# lidar_made_by_apple.net
KiCad netlist of a schematic drawn in EAGLE
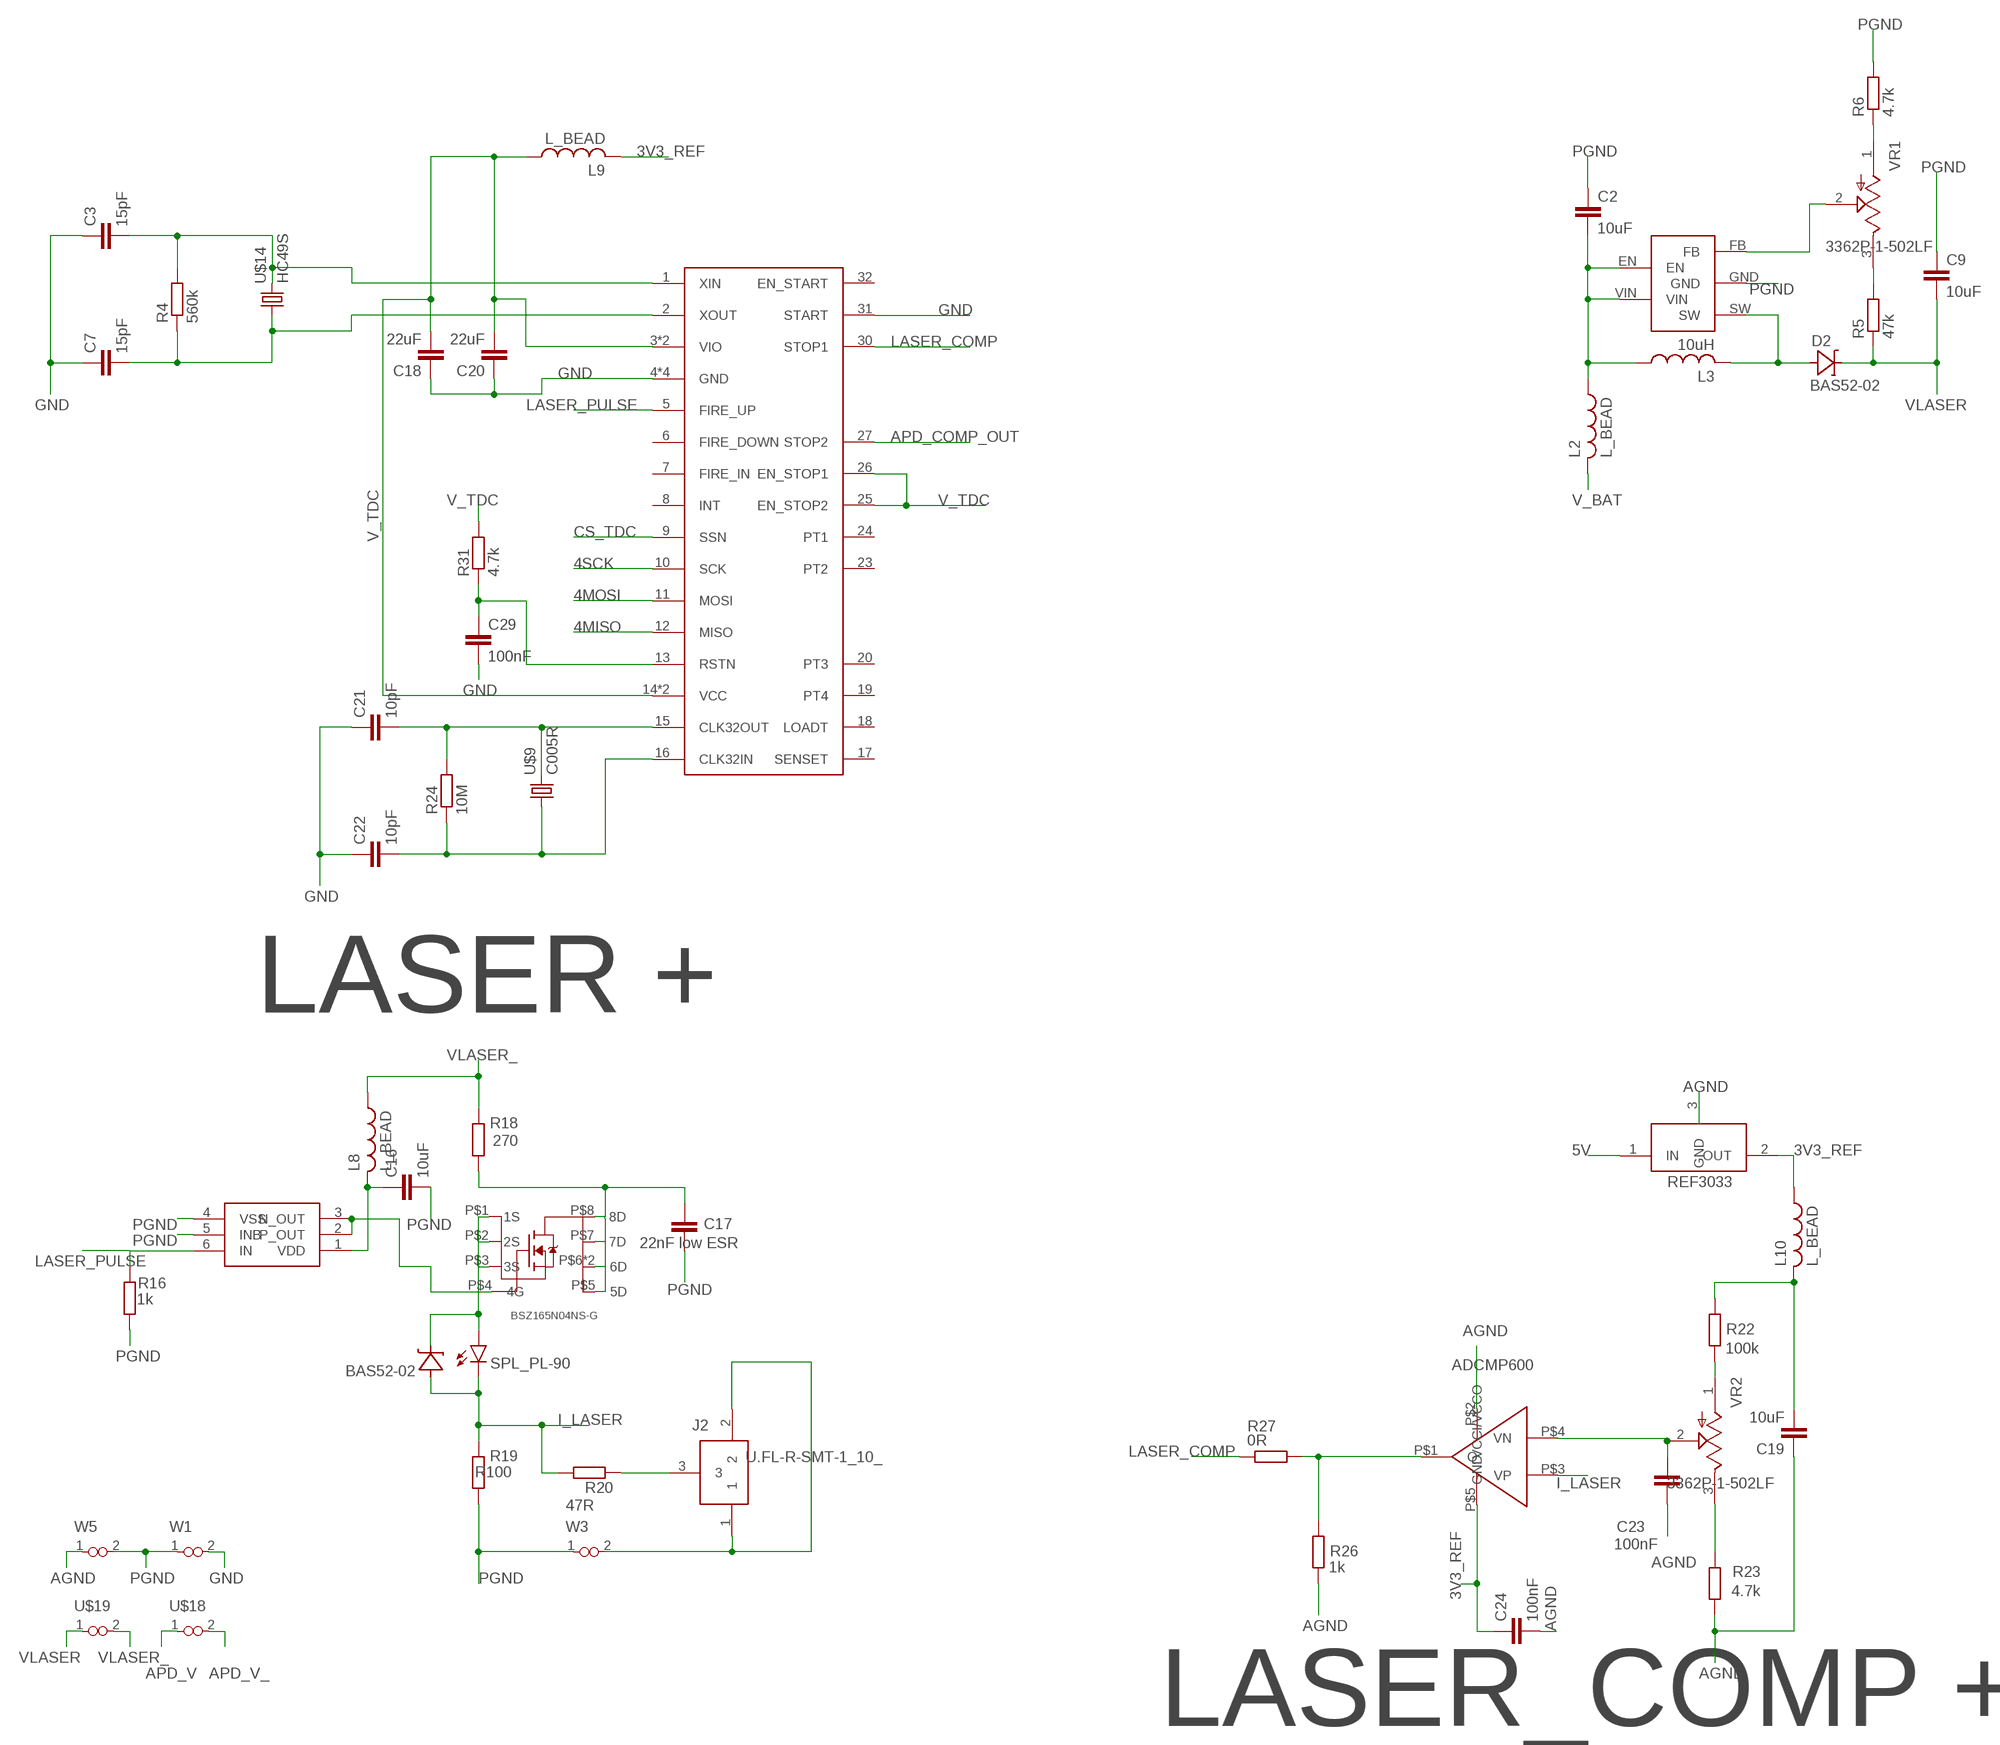
[diagram p0: schematic, sheet 1, part 1 of 2]
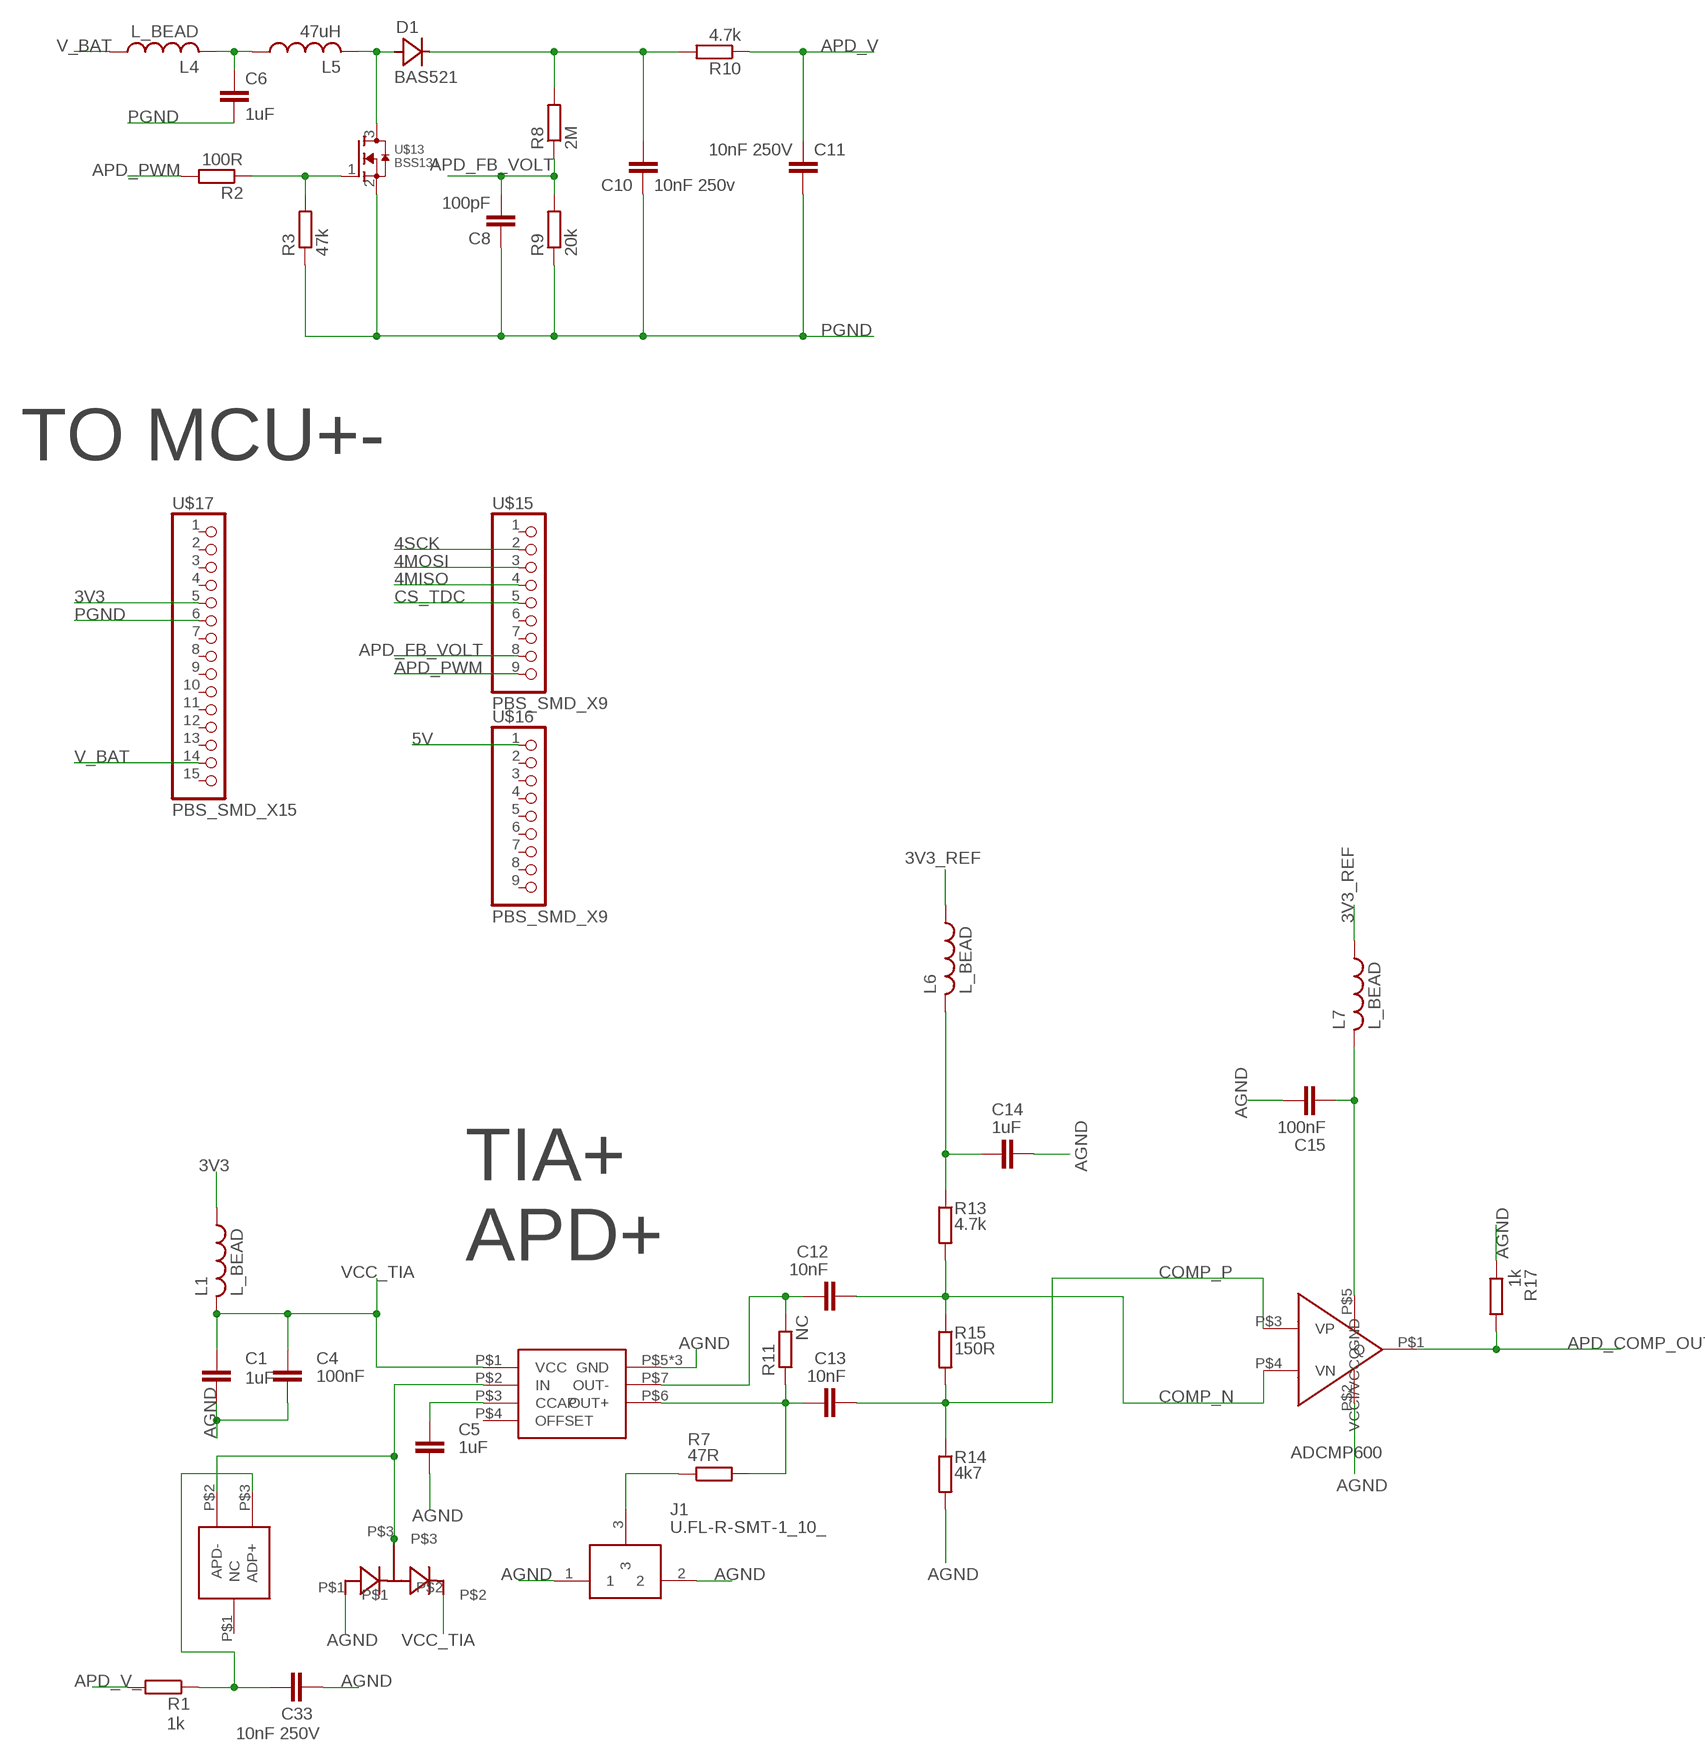
[diagram p1: schematic, sheet 1, part 2 of 2]

(export (version "E")
  (design (tool "Eeschema 10.0.6"))
  (components
    (comp (ref "C1")
      (value "1uF")
      (footprint "eagle-import:C0603")
      (libsource (lib "eagle-import") (part "C-EUC0603"))
    )
    (comp (ref "C2")
      (value "10uF")
      (footprint "eagle-import:C1206")
      (libsource (lib "eagle-import") (part "C-EUC1206"))
    )
    (comp (ref "C3")
      (value "15pF")
      (footprint "eagle-import:C0603")
      (libsource (lib "eagle-import") (part "C-EUC0603"))
    )
    (comp (ref "C4")
      (value "100nF")
      (footprint "eagle-import:C0603")
      (libsource (lib "eagle-import") (part "C-EUC0603"))
    )
    (comp (ref "C5")
      (value "1uF")
      (footprint "eagle-import:C0603")
      (libsource (lib "eagle-import") (part "C-EUC0603"))
    )
    (comp (ref "C6")
      (value "1uF")
      (footprint "eagle-import:C0603")
      (libsource (lib "eagle-import") (part "C-EUC0603"))
    )
    (comp (ref "C7")
      (value "15pF")
      (footprint "eagle-import:C0603")
      (libsource (lib "eagle-import") (part "C-EUC0603"))
    )
    (comp (ref "C8")
      (value "100pF")
      (footprint "eagle-import:C0603")
      (libsource (lib "eagle-import") (part "C-EUC0603"))
    )
    (comp (ref "C9")
      (value "10uF")
      (footprint "eagle-import:C1206")
      (libsource (lib "eagle-import") (part "C-EUC1206"))
    )
    (comp (ref "C10")
      (value "10nF 250v")
      (footprint "eagle-import:C0805")
      (libsource (lib "eagle-import") (part "C-EUC0805"))
    )
    (comp (ref "C11")
      (value "10nF 250V")
      (footprint "eagle-import:C0805")
      (libsource (lib "eagle-import") (part "C-EUC0805"))
    )
    (comp (ref "C12")
      (value "10nF")
      (footprint "eagle-import:C0603")
      (libsource (lib "eagle-import") (part "C-EUC0603"))
    )
    (comp (ref "C13")
      (value "10nF")
      (footprint "eagle-import:C0603")
      (libsource (lib "eagle-import") (part "C-EUC0603"))
    )
    (comp (ref "C14")
      (value "1uF")
      (footprint "eagle-import:C0603")
      (libsource (lib "eagle-import") (part "C-EUC0603"))
    )
    (comp (ref "C15")
      (value "100nF")
      (footprint "eagle-import:C0603")
      (libsource (lib "eagle-import") (part "C-EUC0603"))
    )
    (comp (ref "C16")
      (value "10uF")
      (footprint "eagle-import:C1206")
      (libsource (lib "eagle-import") (part "C-EUC1206"))
    )
    (comp (ref "C17")
      (value "22nF low ESR")
      (footprint "eagle-import:C0603")
      (libsource (lib "eagle-import") (part "C-EUC0603"))
    )
    (comp (ref "C18")
      (value "22uF")
      (footprint "eagle-import:C1206")
      (libsource (lib "eagle-import") (part "C-EUC1206"))
    )
    (comp (ref "C19")
      (value "10uF")
      (footprint "eagle-import:C1206")
      (libsource (lib "eagle-import") (part "C-EUC1206"))
    )
    (comp (ref "C20")
      (value "22uF")
      (footprint "eagle-import:C1206")
      (libsource (lib "eagle-import") (part "C-EUC1206"))
    )
    (comp (ref "C21")
      (value "10pF")
      (footprint "eagle-import:C0603")
      (libsource (lib "eagle-import") (part "C-EUC0603"))
    )
    (comp (ref "C22")
      (value "10pF")
      (footprint "eagle-import:C0603")
      (libsource (lib "eagle-import") (part "C-EUC0603"))
    )
    (comp (ref "C23")
      (value "100nF")
      (footprint "eagle-import:C0603")
      (libsource (lib "eagle-import") (part "C-EUC0603"))
    )
    (comp (ref "C24")
      (value "100nF")
      (footprint "eagle-import:C0603")
      (libsource (lib "eagle-import") (part "C-EUC0603"))
    )
    (comp (ref "C29")
      (value "100nF")
      (footprint "eagle-import:C0603")
      (libsource (lib "eagle-import") (part "C-EUC0603"))
    )
    (comp (ref "C33")
      (value "10nF 250V")
      (footprint "eagle-import:C0805")
      (libsource (lib "eagle-import") (part "C-EUC0805"))
    )
    (comp (ref "D1")
      (value "BAS521")
      (footprint "eagle-import:SOD523")
      (libsource (lib "eagle-import") (part "BAS521"))
    )
    (comp (ref "D2")
      (value "BAS52-02")
      (footprint "eagle-import:SOD523")
      (libsource (lib "eagle-import") (part "BAS52-02"))
    )
    (comp (ref "D6")
      (value "BAV99")
      (footprint "eagle-import:BAV99")
      (libsource (lib "eagle-import") (part "BAV99"))
    )
    (comp (ref "J1")
      (value "U.FL-R-SMT-1_10_")
      (footprint "eagle-import:U.FL-R-SMT-1(10)")
      (fields
        (field (name "ARROW_PART_NUMBER") "U.FL-R-SMT-1(10)")
        (field (name "MOUSER_PART_NUMBER") "798-U.FL-R-SMT-110")
      )
      (libsource (lib "eagle-import") (part "U.FL-R-SMT-1_10_"))
    )
    (comp (ref "J2")
      (value "U.FL-R-SMT-1_10_")
      (footprint "eagle-import:U.FL-R-SMT-1(10)")
      (fields
        (field (name "ARROW_PART_NUMBER") "U.FL-R-SMT-1(10)")
        (field (name "MOUSER_PART_NUMBER") "798-U.FL-R-SMT-110")
      )
      (libsource (lib "eagle-import") (part "U.FL-R-SMT-1_10_"))
    )
    (comp (ref "L1")
      (value "L_BEAD")
      (footprint "eagle-import:L_BEAD")
      (libsource (lib "eagle-import") (part "L_BEAD"))
    )
    (comp (ref "L2")
      (value "L_BEAD")
      (footprint "eagle-import:L_BEAD")
      (libsource (lib "eagle-import") (part "L_BEAD"))
    )
    (comp (ref "L3")
      (value "10uH")
      (footprint "eagle-import:L_12X12")
      (libsource (lib "eagle-import") (part "L_15MKH"))
    )
    (comp (ref "L4")
      (value "L_BEAD")
      (footprint "eagle-import:L_BEAD")
      (libsource (lib "eagle-import") (part "L_BEAD"))
    )
    (comp (ref "L5")
      (value "47uH")
      (footprint "eagle-import:1210")
      (libsource (lib "eagle-import") (part "CM322522-470KL"))
    )
    (comp (ref "L6")
      (value "L_BEAD")
      (footprint "eagle-import:L_BEAD")
      (libsource (lib "eagle-import") (part "L_BEAD"))
    )
    (comp (ref "L7")
      (value "L_BEAD")
      (footprint "eagle-import:L_BEAD")
      (libsource (lib "eagle-import") (part "L_BEAD"))
    )
    (comp (ref "L8")
      (value "L_BEAD")
      (footprint "eagle-import:L_BEAD")
      (libsource (lib "eagle-import") (part "L_BEAD"))
    )
    (comp (ref "L9")
      (value "L_BEAD")
      (footprint "eagle-import:L_BEAD")
      (libsource (lib "eagle-import") (part "L_BEAD"))
    )
    (comp (ref "L10")
      (value "L_BEAD")
      (footprint "eagle-import:L_BEAD")
      (libsource (lib "eagle-import") (part "L_BEAD"))
    )
    (comp (ref "R1")
      (value "1k")
      (footprint "eagle-import:R0603")
      (libsource (lib "eagle-import") (part "R-EU_R0603"))
    )
    (comp (ref "R2")
      (value "100R")
      (footprint "eagle-import:R0603")
      (libsource (lib "eagle-import") (part "R-EU_R0603"))
    )
    (comp (ref "R3")
      (value "47k")
      (footprint "eagle-import:R0603")
      (libsource (lib "eagle-import") (part "R-EU_R0603"))
    )
    (comp (ref "R4")
      (value "560k")
      (footprint "eagle-import:R0603")
      (libsource (lib "eagle-import") (part "R-EU_R0603"))
    )
    (comp (ref "R5")
      (value "47k")
      (footprint "eagle-import:R0603")
      (libsource (lib "eagle-import") (part "R-EU_R0603"))
    )
    (comp (ref "R6")
      (value "4.7k")
      (footprint "eagle-import:R0603")
      (libsource (lib "eagle-import") (part "R-EU_R0603"))
    )
    (comp (ref "R7")
      (value "47R")
      (footprint "eagle-import:R0603")
      (libsource (lib "eagle-import") (part "R-EU_R0603"))
    )
    (comp (ref "R8")
      (value "2M")
      (footprint "eagle-import:R0603")
      (libsource (lib "eagle-import") (part "R-EU_R0603"))
    )
    (comp (ref "R9")
      (value "20k")
      (footprint "eagle-import:R0603")
      (libsource (lib "eagle-import") (part "R-EU_R0603"))
    )
    (comp (ref "R10")
      (value "4.7k")
      (footprint "eagle-import:R0603")
      (libsource (lib "eagle-import") (part "R-EU_R0603"))
    )
    (comp (ref "R11")
      (value "NC")
      (footprint "eagle-import:R0603")
      (libsource (lib "eagle-import") (part "R-EU_R0603"))
    )
    (comp (ref "R13")
      (value "4.7k")
      (footprint "eagle-import:R0603")
      (libsource (lib "eagle-import") (part "R-EU_R0603"))
    )
    (comp (ref "R14")
      (value "4k7")
      (footprint "eagle-import:R0603")
      (libsource (lib "eagle-import") (part "R-EU_R0603"))
    )
    (comp (ref "R15")
      (value "150R")
      (footprint "eagle-import:R0603")
      (libsource (lib "eagle-import") (part "R-EU_R0603"))
    )
    (comp (ref "R16")
      (value "1k")
      (footprint "eagle-import:R0603")
      (libsource (lib "eagle-import") (part "R-EU_R0603"))
    )
    (comp (ref "R17")
      (value "1k")
      (footprint "eagle-import:R0603")
      (libsource (lib "eagle-import") (part "R-EU_R0603"))
    )
    (comp (ref "R18")
      (value "270")
      (footprint "eagle-import:R0603")
      (libsource (lib "eagle-import") (part "R-EU_R0603"))
    )
    (comp (ref "R19")
      (value "R100")
      (footprint "eagle-import:R2512")
      (libsource (lib "eagle-import") (part "R-EU_R2512"))
    )
    (comp (ref "R20")
      (value "47R")
      (footprint "eagle-import:R0603")
      (libsource (lib "eagle-import") (part "R-EU_R0603"))
    )
    (comp (ref "R22")
      (value "100k")
      (footprint "eagle-import:R0603")
      (libsource (lib "eagle-import") (part "R-EU_R0603"))
    )
    (comp (ref "R23")
      (value "4.7k")
      (footprint "eagle-import:R0603")
      (libsource (lib "eagle-import") (part "R-EU_R0603"))
    )
    (comp (ref "R24")
      (value "10M")
      (footprint "eagle-import:R0603")
      (libsource (lib "eagle-import") (part "R-EU_R0603"))
    )
    (comp (ref "R26")
      (value "1k")
      (footprint "eagle-import:R0603")
      (libsource (lib "eagle-import") (part "R-EU_R0603"))
    )
    (comp (ref "R27")
      (value "0R")
      (footprint "eagle-import:R0603")
      (libsource (lib "eagle-import") (part "R-EU_R0603"))
    )
    (comp (ref "R31")
      (value "4.7k")
      (footprint "eagle-import:R0603")
      (libsource (lib "eagle-import") (part "R-EU_R0603"))
    )
    (comp (ref "REF3033")
      (value "REF3033")
      (footprint "eagle-import:SOT23-3")
      (libsource (lib "eagle-import") (part "REF3033"))
    )
    (comp (ref "U$2")
      (value "BSZ165N04NS-G")
      (footprint "eagle-import:BSZ165N04NS-G")
      (libsource (lib "eagle-import") (part "BSZ165N04NS-G"))
    )
    (comp (ref "U$3")
      (value "BAS52-02")
      (footprint "eagle-import:SOD523")
      (libsource (lib "eagle-import") (part "BAS52-02"))
    )
    (comp (ref "U$4")
      (value "ADCMP600")
      (footprint "eagle-import:ADCMP600")
      (libsource (lib "eagle-import") (part "ADCMP600"))
    )
    (comp (ref "U$5")
      (value "MAX40658-8-TDFN-3X3MM")
      (footprint "eagle-import:MAX40658-8-TDFN-3X3MM")
      (libsource (lib "eagle-import") (part "MAX40658-8-TDFN-3X3MM"))
    )
    (comp (ref "U$6")
      (value "SPL_PL-90")
      (footprint "eagle-import:SPL_PL-90")
      (libsource (lib "eagle-import") (part "SPL_PL-90"))
    )
    (comp (ref "U$7")
      (value "MTAPD-07-013")
      (footprint "eagle-import:MAPD-07-013")
      (libsource (lib "eagle-import") (part "MTAPD-07-013"))
    )
    (comp (ref "U$8")
      (value "ADCMP600")
      (footprint "eagle-import:ADCMP600")
      (libsource (lib "eagle-import") (part "ADCMP600"))
    )
    (comp (ref "U$9")
      (value "C005R")
      (footprint "eagle-import:C005R")
      (libsource (lib "eagle-import") (part "C005R"))
    )
    (comp (ref "U$10")
      (value "TDC-GP21")
      (footprint "eagle-import:TDC-GP21")
      (libsource (lib "eagle-import") (part "TDC-GP21"))
    )
    (comp (ref "U$11")
      (value "MIC2288")
      (footprint "eagle-import:MIC2288")
      (libsource (lib "eagle-import") (part "MIC2288"))
    )
    (comp (ref "U$12")
      (value "LM5114")
      (footprint "eagle-import:SOT23-6")
      (libsource (lib "eagle-import") (part "LM5114"))
    )
    (comp (ref "U$13")
      (value "BSS131")
      (footprint "eagle-import:SOT23-3")
      (libsource (lib "eagle-import") (part "BSS131"))
    )
    (comp (ref "U$14")
      (value "HC49S")
      (footprint "eagle-import:HC49S")
      (libsource (lib "eagle-import") (part "HC49S"))
    )
    (comp (ref "U$15")
      (value "PBS_SMD_X9")
      (footprint "eagle-import:PBS_SMD_X9")
      (libsource (lib "eagle-import") (part "PBS_SMD_X9"))
    )
    (comp (ref "U$16")
      (value "PBS_SMD_X9")
      (footprint "eagle-import:PBS_SMD_X9")
      (libsource (lib "eagle-import") (part "PBS_SMD_X9"))
    )
    (comp (ref "U$17")
      (value "PBS_SMD_X15")
      (footprint "eagle-import:PBD_SMD_X15")
      (libsource (lib "eagle-import") (part "PBS_SMD_X15"))
    )
    (comp (ref "U$18")
      (value "VIAS-CONNECT")
      (footprint "eagle-import:VIAS-CONNECT")
      (libsource (lib "eagle-import") (part "VIAS-CONNECT"))
    )
    (comp (ref "U$19")
      (value "VIAS-CONNECT")
      (footprint "eagle-import:VIAS-CONNECT")
      (libsource (lib "eagle-import") (part "VIAS-CONNECT"))
    )
    (comp (ref "VR1")
      (value "3362P-1-502LF")
      (footprint "eagle-import:TRIM_3362P-1-502LF")
      (fields (field (name "MF") "Bourns"))
      (libsource (lib "eagle-import") (part "3362P-1-502LF"))
    )
    (comp (ref "VR2")
      (value "3362P-1-502LF")
      (footprint "eagle-import:TRIM_3362P-1-502LF")
      (fields (field (name "MF") "Bourns"))
      (libsource (lib "eagle-import") (part "3362P-1-502LF"))
    )
    (comp (ref "W1")
      (value "VIAS-CONNECT")
      (footprint "eagle-import:VIAS-CONNECT")
      (libsource (lib "eagle-import") (part "VIAS-CONNECT"))
    )
    (comp (ref "W3")
      (value "VIAS-CONNECT")
      (footprint "eagle-import:VIAS-CONNECT")
      (libsource (lib "eagle-import") (part "VIAS-CONNECT"))
    )
    (comp (ref "W5")
      (value "VIAS-CONNECT")
      (footprint "eagle-import:VIAS-CONNECT")
      (libsource (lib "eagle-import") (part "VIAS-CONNECT"))
    )
  )
  (nets
    (net (code "1") (name "/3V3") (class "Default")
      (node (ref "L1") (pin "1") (pinfunction "1_1") (pintype "passive"))
      (node (ref "U$17") (pin "5") (pinfunction "5_5") (pintype "passive"))
    )
    (net (code "2") (name "/3V3_REF") (class "Default")
      (node (ref "C24") (pin "1") (pinfunction "1_1") (pintype "passive"))
      (node (ref "L10") (pin "1") (pinfunction "1_1") (pintype "passive"))
      (node (ref "L6") (pin "1") (pinfunction "1_1") (pintype "passive"))
      (node (ref "L7") (pin "1") (pinfunction "1_1") (pintype "passive"))
      (node (ref "L9") (pin "2") (pinfunction "2_2") (pintype "passive"))
      (node (ref "REF3033") (pin "2") (pinfunction "OUT_2") (pintype "output"))
      (node (ref "U$4") (pin "P$5") (pinfunction "VCCI/VCCO_P$5") (pintype "bidirectional"))
    )
    (net (code "3") (name "/4MISO") (class "Default")
      (node (ref "U$10") (pin "12") (pinfunction "MISO_12") (pintype "bidirectional"))
      (node (ref "U$15") (pin "4") (pinfunction "4_4") (pintype "passive"))
    )
    (net (code "4") (name "/4MOSI") (class "Default")
      (node (ref "U$10") (pin "11") (pinfunction "MOSI_11") (pintype "bidirectional"))
      (node (ref "U$15") (pin "3") (pinfunction "3_3") (pintype "passive"))
    )
    (net (code "5") (name "/4SCK") (class "Default")
      (node (ref "U$10") (pin "10") (pinfunction "SCK_10") (pintype "bidirectional"))
      (node (ref "U$15") (pin "2") (pinfunction "2_2") (pintype "passive"))
    )
    (net (code "6") (name "/5V") (class "Default")
      (node (ref "REF3033") (pin "1") (pinfunction "IN_1") (pintype "input"))
      (node (ref "U$16") (pin "1") (pinfunction "1_1") (pintype "passive"))
    )
    (net (code "7") (name "/AGND") (class "Default")
      (node (ref "C1") (pin "2") (pinfunction "2_2") (pintype "passive"))
      (node (ref "C14") (pin "1") (pinfunction "1_1") (pintype "passive"))
      (node (ref "C15") (pin "1") (pinfunction "1_1") (pintype "passive"))
      (node (ref "C19") (pin "1") (pinfunction "1_1") (pintype "passive"))
      (node (ref "C23") (pin "2") (pinfunction "2_2") (pintype "passive"))
      (node (ref "C24") (pin "2") (pinfunction "2_2") (pintype "passive"))
      (node (ref "C33") (pin "2") (pinfunction "2_2") (pintype "passive"))
      (node (ref "C4") (pin "2") (pinfunction "2_2") (pintype "passive"))
      (node (ref "C5") (pin "2") (pinfunction "2_2") (pintype "passive"))
      (node (ref "D6") (pin "P$1") (pinfunction "P$1_P$1") (pintype "bidirectional"))
      (node (ref "J1") (pin "1") (pinfunction "1_1") (pintype "bidirectional"))
      (node (ref "J1") (pin "2") (pinfunction "2_2") (pintype "bidirectional"))
      (node (ref "R14") (pin "2") (pinfunction "2_2") (pintype "passive"))
      (node (ref "R17") (pin "1") (pinfunction "1_1") (pintype "passive"))
      (node (ref "R23") (pin "1") (pinfunction "1_1") (pintype "passive"))
      (node (ref "R26") (pin "1") (pinfunction "1_1") (pintype "passive"))
      (node (ref "REF3033") (pin "3") (pinfunction "GND_3") (pintype "power_in"))
      (node (ref "U$4") (pin "P$2") (pinfunction "GND_P$2") (pintype "bidirectional"))
      (node (ref "U$5") (pin "P$5") (pinfunction "GND_P$5") (pintype "bidirectional"))
      (node (ref "U$5") (pin "P$8") (pinfunction "GND_P$8") (pintype "bidirectional"))
      (node (ref "U$5") (pin "P$9") (pinfunction "GND_P$9") (pintype "bidirectional"))
      (node (ref "U$8") (pin "P$2") (pinfunction "GND_P$2") (pintype "bidirectional"))
      (node (ref "W5") (pin "1") (pinfunction "1_1") (pintype "passive"))
    )
    (net (code "8") (name "/APD_COMP_OUT") (class "Default")
      (node (ref "R17") (pin "2") (pinfunction "2_2") (pintype "passive"))
      (node (ref "U$10") (pin "27") (pinfunction "STOP2_27") (pintype "bidirectional"))
      (node (ref "U$8") (pin "P$1") (pinfunction "Q_P$1") (pintype "bidirectional"))
    )
    (net (code "9") (name "/APD_FB_VOLT") (class "Default")
      (node (ref "C8") (pin "2") (pinfunction "2_2") (pintype "passive"))
      (node (ref "R8") (pin "1") (pinfunction "1_1") (pintype "passive"))
      (node (ref "R9") (pin "2") (pinfunction "2_2") (pintype "passive"))
      (node (ref "U$15") (pin "8") (pinfunction "8_8") (pintype "passive"))
    )
    (net (code "10") (name "/APD_PWM") (class "Default")
      (node (ref "R2") (pin "2") (pinfunction "2_2") (pintype "passive"))
      (node (ref "U$15") (pin "9") (pinfunction "9_9") (pintype "passive"))
    )
    (net (code "11") (name "/APD_V") (class "Default")
      (node (ref "C11") (pin "2") (pinfunction "2_2") (pintype "passive"))
      (node (ref "R10") (pin "1") (pinfunction "1_1") (pintype "passive"))
      (node (ref "U$18") (pin "1") (pinfunction "1_1") (pintype "passive"))
    )
    (net (code "12") (name "/APD_V_") (class "Default")
      (node (ref "R1") (pin "2") (pinfunction "2_2") (pintype "passive"))
      (node (ref "U$18") (pin "2") (pinfunction "2_2") (pintype "passive"))
    )
    (net (code "13") (name "/COMP_N") (class "Default")
      (node (ref "C12") (pin "2") (pinfunction "2_2") (pintype "passive"))
      (node (ref "R13") (pin "2") (pinfunction "2_2") (pintype "passive"))
      (node (ref "R15") (pin "1") (pinfunction "1_1") (pintype "passive"))
      (node (ref "U$8") (pin "P$4") (pinfunction "VN_P$4") (pintype "bidirectional"))
    )
    (net (code "14") (name "/COMP_P") (class "Default")
      (node (ref "C13") (pin "2") (pinfunction "2_2") (pintype "passive"))
      (node (ref "R14") (pin "1") (pinfunction "1_1") (pintype "passive"))
      (node (ref "R15") (pin "2") (pinfunction "2_2") (pintype "passive"))
      (node (ref "U$8") (pin "P$3") (pinfunction "VP_P$3") (pintype "bidirectional"))
    )
    (net (code "15") (name "/CS_TDC") (class "Default")
      (node (ref "U$10") (pin "9") (pinfunction "SSN_9") (pintype "bidirectional"))
      (node (ref "U$15") (pin "5") (pinfunction "5_5") (pintype "passive"))
    )
    (net (code "16") (name "/GND") (class "Default")
      (node (ref "C18") (pin "1") (pinfunction "1_1") (pintype "passive"))
      (node (ref "C20") (pin "1") (pinfunction "1_1") (pintype "passive"))
      (node (ref "C21") (pin "1") (pinfunction "1_1") (pintype "passive"))
      (node (ref "C22") (pin "1") (pinfunction "1_1") (pintype "passive"))
      (node (ref "C29") (pin "2") (pinfunction "2_2") (pintype "passive"))
      (node (ref "C3") (pin "1") (pinfunction "1_1") (pintype "passive"))
      (node (ref "C7") (pin "1") (pinfunction "1_1") (pintype "passive"))
      (node (ref "U$10") (pin "21") (pinfunction "GND_21") (pintype "bidirectional"))
      (node (ref "U$10") (pin "28") (pinfunction "GND_28") (pintype "bidirectional"))
      (node (ref "U$10") (pin "31") (pinfunction "START_31") (pintype "bidirectional"))
      (node (ref "U$10") (pin "4") (pinfunction "GND_4") (pintype "bidirectional"))
      (node (ref "U$10") (pin "P$1") (pinfunction "GND_P$1") (pintype "bidirectional"))
      (node (ref "W1") (pin "2") (pinfunction "2_2") (pintype "passive"))
    )
    (net (code "17") (name "/I_LASER") (class "Default")
      (node (ref "R19") (pin "2") (pinfunction "2_2") (pintype "passive"))
      (node (ref "R20") (pin "2") (pinfunction "2_2") (pintype "passive"))
      (node (ref "U$3") (pin "P$2") (pinfunction "A_P$2") (pintype "passive"))
      (node (ref "U$4") (pin "P$3") (pinfunction "VP_P$3") (pintype "bidirectional"))
      (node (ref "U$6") (pin "P$2") (pinfunction "C_P$2") (pintype "passive"))
    )
    (net (code "18") (name "/LASER_COMP") (class "Default")
      (node (ref "R27") (pin "1") (pinfunction "1_1") (pintype "passive"))
      (node (ref "U$10") (pin "30") (pinfunction "STOP1_30") (pintype "bidirectional"))
    )
    (net (code "19") (name "/LASER_PULSE") (class "Default")
      (node (ref "R16") (pin "2") (pinfunction "2_2") (pintype "passive"))
      (node (ref "U$10") (pin "5") (pinfunction "FIRE_UP_5") (pintype "bidirectional"))
      (node (ref "U$12") (pin "6") (pinfunction "IN_6") (pintype "bidirectional"))
    )
    (net (code "20") (name "/PGND") (class "Default")
      (node (ref "C10") (pin "1") (pinfunction "1_1") (pintype "passive"))
      (node (ref "C11") (pin "1") (pinfunction "1_1") (pintype "passive"))
      (node (ref "C16") (pin "2") (pinfunction "2_2") (pintype "passive"))
      (node (ref "C17") (pin "1") (pinfunction "1_1") (pintype "passive"))
      (node (ref "C2") (pin "1") (pinfunction "1_1") (pintype "passive"))
      (node (ref "C6") (pin "2") (pinfunction "2_2") (pintype "passive"))
      (node (ref "C8") (pin "1") (pinfunction "1_1") (pintype "passive"))
      (node (ref "C9") (pin "1") (pinfunction "1_1") (pintype "passive"))
      (node (ref "R16") (pin "1") (pinfunction "1_1") (pintype "passive"))
      (node (ref "R19") (pin "1") (pinfunction "1_1") (pintype "passive"))
      (node (ref "R3") (pin "1") (pinfunction "1_1") (pintype "passive"))
      (node (ref "R6") (pin "2") (pinfunction "2_2") (pintype "passive"))
      (node (ref "R9") (pin "1") (pinfunction "1_1") (pintype "passive"))
      (node (ref "U$11") (pin "GND") (pinfunction "GND_GND") (pintype "bidirectional"))
      (node (ref "U$12") (pin "4") (pinfunction "VSS_4") (pintype "bidirectional"))
      (node (ref "U$12") (pin "5") (pinfunction "INB_5") (pintype "bidirectional"))
      (node (ref "U$13") (pin "2") (pinfunction "S_2") (pintype "bidirectional"))
      (node (ref "U$17") (pin "6") (pinfunction "6_6") (pintype "passive"))
      (node (ref "W1") (pin "1") (pinfunction "1_1") (pintype "passive"))
      (node (ref "W3") (pin "1") (pinfunction "1_1") (pintype "passive"))
      (node (ref "W5") (pin "2") (pinfunction "2_2") (pintype "passive"))
    )
    (net (code "21") (name "/VCC_TIA") (class "Default")
      (node (ref "C1") (pin "1") (pinfunction "1_1") (pintype "passive"))
      (node (ref "C4") (pin "1") (pinfunction "1_1") (pintype "passive"))
      (node (ref "D6") (pin "P$2") (pinfunction "P$2_P$2") (pintype "bidirectional"))
      (node (ref "L1") (pin "2") (pinfunction "2_2") (pintype "passive"))
      (node (ref "U$5") (pin "P$1") (pinfunction "VCC_P$1") (pintype "bidirectional"))
    )
    (net (code "22") (name "/VLASER") (class "Default")
      (node (ref "C9") (pin "2") (pinfunction "2_2") (pintype "passive"))
      (node (ref "D2") (pin "P$1") (pinfunction "C_P$1") (pintype "passive"))
      (node (ref "R5") (pin "1") (pinfunction "1_1") (pintype "passive"))
      (node (ref "U$19") (pin "1") (pinfunction "1_1") (pintype "passive"))
    )
    (net (code "23") (name "/VLASER_") (class "Default")
      (node (ref "L8") (pin "1") (pinfunction "1_1") (pintype "passive"))
      (node (ref "R18") (pin "2") (pinfunction "2_2") (pintype "passive"))
      (node (ref "U$19") (pin "2") (pinfunction "2_2") (pintype "passive"))
    )
    (net (code "24") (name "/V_BAT") (class "Default")
      (node (ref "L2") (pin "2") (pinfunction "2_2") (pintype "passive"))
      (node (ref "L4") (pin "1") (pinfunction "1_1") (pintype "passive"))
      (node (ref "U$17") (pin "14") (pinfunction "14_14") (pintype "passive"))
    )
    (net (code "25") (name "/V_TDC") (class "Default")
      (node (ref "C18") (pin "2") (pinfunction "2_2") (pintype "passive"))
      (node (ref "C20") (pin "2") (pinfunction "2_2") (pintype "passive"))
      (node (ref "L9") (pin "1") (pinfunction "1_1") (pintype "passive"))
      (node (ref "R31") (pin "2") (pinfunction "2_2") (pintype "passive"))
      (node (ref "U$10") (pin "14") (pinfunction "VCC_14") (pintype "bidirectional"))
      (node (ref "U$10") (pin "22") (pinfunction "VIO_22") (pintype "bidirectional"))
      (node (ref "U$10") (pin "25") (pinfunction "EN_STOP2_25") (pintype "bidirectional"))
      (node (ref "U$10") (pin "26") (pinfunction "EN_STOP1_26") (pintype "bidirectional"))
      (node (ref "U$10") (pin "29") (pinfunction "VCC_29") (pintype "bidirectional"))
      (node (ref "U$10") (pin "3") (pinfunction "VIO_3") (pintype "bidirectional"))
    )
    (net (code "26") (name "Net-(C6-Pad1)") (class "Default")
      (node (ref "C6") (pin "1") (pinfunction "1_1") (pintype "passive"))
      (node (ref "L4") (pin "2") (pinfunction "2_2") (pintype "passive"))
      (node (ref "L5") (pin "1") (pinfunction "1_1") (pintype "passive"))
    )
    (net (code "27") (name "Net-(C14-Pad2)") (class "Default")
      (node (ref "C14") (pin "2") (pinfunction "2_2") (pintype "passive"))
      (node (ref "L6") (pin "2") (pinfunction "2_2") (pintype "passive"))
      (node (ref "R13") (pin "1") (pinfunction "1_1") (pintype "passive"))
    )
    (net (code "28") (name "Net-(C19-Pad2)") (class "Default")
      (node (ref "C19") (pin "2") (pinfunction "2_2") (pintype "passive"))
      (node (ref "L10") (pin "2") (pinfunction "2_2") (pintype "passive"))
      (node (ref "R22") (pin "2") (pinfunction "2_2") (pintype "passive"))
    )
    (net (code "29") (name "Net-(D1-1)") (class "Default")
      (node (ref "C10") (pin "2") (pinfunction "2_2") (pintype "passive"))
      (node (ref "D1") (pin "P$1") (pinfunction "1_P$1") (pintype "passive"))
      (node (ref "R10") (pin "2") (pinfunction "2_2") (pintype "passive"))
      (node (ref "R8") (pin "2") (pinfunction "2_2") (pintype "passive"))
    )
    (net (code "30") (name "Net-(D1-2)") (class "Default")
      (node (ref "D1") (pin "P$2") (pinfunction "2_P$2") (pintype "passive"))
      (node (ref "L5") (pin "2") (pinfunction "2_2") (pintype "passive"))
      (node (ref "U$13") (pin "3") (pinfunction "D_3") (pintype "bidirectional"))
    )
    (net (code "31") (name "Net-(D2-A)") (class "Default")
      (node (ref "D2") (pin "P$2") (pinfunction "A_P$2") (pintype "passive"))
      (node (ref "L3") (pin "P$2") (pinfunction "2_P$2") (pintype "passive"))
      (node (ref "U$11") (pin "SW") (pinfunction "SW_SW") (pintype "bidirectional"))
    )
    (net (code "32") (name "Net-(J1-Pad3)") (class "Default")
      (node (ref "J1") (pin "3") (pinfunction "3_3") (pintype "bidirectional"))
      (node (ref "R7") (pin "1") (pinfunction "1_1") (pintype "passive"))
    )
    (net (code "33") (name "Net-(J2-Pad1)") (class "Default")
      (node (ref "J2") (pin "1") (pinfunction "1_1") (pintype "bidirectional"))
      (node (ref "J2") (pin "2") (pinfunction "2_2") (pintype "bidirectional"))
      (node (ref "W3") (pin "2") (pinfunction "2_2") (pintype "passive"))
    )
    (net (code "34") (name "Net-(J2-Pad3)") (class "Default")
      (node (ref "J2") (pin "3") (pinfunction "3_3") (pintype "bidirectional"))
      (node (ref "R20") (pin "1") (pinfunction "1_1") (pintype "passive"))
    )
    (net (code "35") (name "Net-(L3-1)") (class "Default")
      (node (ref "C2") (pin "2") (pinfunction "2_2") (pintype "passive"))
      (node (ref "L2") (pin "1") (pinfunction "1_1") (pintype "passive"))
      (node (ref "L3") (pin "P$1") (pinfunction "1_P$1") (pintype "passive"))
      (node (ref "U$11") (pin "EN") (pinfunction "EN_EN") (pintype "bidirectional"))
      (node (ref "U$11") (pin "VIN") (pinfunction "VIN_VIN") (pintype "bidirectional"))
    )
    (net (code "36") (name "Net-(U$2-1S)") (class "Default")
      (node (ref "U$2") (pin "P$1") (pinfunction "1S_P$1") (pintype "bidirectional"))
      (node (ref "U$2") (pin "P$2") (pinfunction "2S_P$2") (pintype "bidirectional"))
      (node (ref "U$2") (pin "P$3") (pinfunction "3S_P$3") (pintype "bidirectional"))
      (node (ref "U$3") (pin "P$1") (pinfunction "C_P$1") (pintype "passive"))
      (node (ref "U$6") (pin "P$1") (pinfunction "A_P$1") (pintype "passive"))
    )
    (net (code "37") (name "Net-(U$2-5D)") (class "Default")
      (node (ref "C17") (pin "2") (pinfunction "2_2") (pintype "passive"))
      (node (ref "R18") (pin "1") (pinfunction "1_1") (pintype "passive"))
      (node (ref "U$2") (pin "P$5") (pinfunction "5D_P$5") (pintype "bidirectional"))
      (node (ref "U$2") (pin "P$6") (pinfunction "6D_P$6") (pintype "bidirectional"))
      (node (ref "U$2") (pin "P$7") (pinfunction "7D_P$7") (pintype "bidirectional"))
      (node (ref "U$2") (pin "P$8") (pinfunction "8D_P$8") (pintype "bidirectional"))
      (node (ref "U$2") (pin "P$9") (pinfunction "6D_P$9") (pintype "bidirectional"))
    )
    (net (code "38") (name "Net-(U$4-Q)") (class "Default")
      (node (ref "R26") (pin "2") (pinfunction "2_2") (pintype "passive"))
      (node (ref "R27") (pin "2") (pinfunction "2_2") (pintype "passive"))
      (node (ref "U$4") (pin "P$1") (pinfunction "Q_P$1") (pintype "bidirectional"))
    )
    (net (code "39") (name "Net-(U$4-VN)") (class "Default")
      (node (ref "C23") (pin "1") (pinfunction "1_1") (pintype "passive"))
      (node (ref "U$4") (pin "P$4") (pinfunction "VN_P$4") (pintype "bidirectional"))
      (node (ref "VR2") (pin "2") (pinfunction "WIPER_2") (pintype "passive"))
    )
    (net (code "40") (name "Net-(U$5-CCAP)") (class "Default")
      (node (ref "C5") (pin "1") (pinfunction "1_1") (pintype "passive"))
      (node (ref "U$5") (pin "P$3") (pinfunction "CCAP_P$3") (pintype "bidirectional"))
    )
    (net (code "41") (name "Net-(U$5-IN)") (class "Default")
      (node (ref "D6") (pin "P$3") (pinfunction "P$3_P$3") (pintype "bidirectional"))
      (node (ref "U$5") (pin "P$2") (pinfunction "IN_P$2") (pintype "bidirectional"))
      (node (ref "U$7") (pin "P$2") (pinfunction "APD-_P$2") (pintype "bidirectional"))
    )
    (net (code "42") (name "Net-(U$5-OUT+)") (class "Default")
      (node (ref "C13") (pin "1") (pinfunction "1_1") (pintype "passive"))
      (node (ref "R11") (pin "1") (pinfunction "1_1") (pintype "passive"))
      (node (ref "R7") (pin "2") (pinfunction "2_2") (pintype "passive"))
      (node (ref "U$5") (pin "P$6") (pinfunction "OUT+_P$6") (pintype "bidirectional"))
    )
    (net (code "43") (name "Net-(U$5-OUT-)") (class "Default")
      (node (ref "C12") (pin "1") (pinfunction "1_1") (pintype "passive"))
      (node (ref "R11") (pin "2") (pinfunction "2_2") (pintype "passive"))
      (node (ref "U$5") (pin "P$7") (pinfunction "OUT-_P$7") (pintype "bidirectional"))
    )
    (net (code "44") (name "Net-(U$7-ADP+)") (class "Default")
      (node (ref "C33") (pin "1") (pinfunction "1_1") (pintype "passive"))
      (node (ref "R1") (pin "1") (pinfunction "1_1") (pintype "passive"))
      (node (ref "U$7") (pin "P$3") (pinfunction "ADP+_P$3") (pintype "bidirectional"))
    )
    (net (code "45") (name "Net-(U$8-VCCI{slash}VCCO)") (class "Default")
      (node (ref "C15") (pin "2") (pinfunction "2_2") (pintype "passive"))
      (node (ref "L7") (pin "2") (pinfunction "2_2") (pintype "passive"))
      (node (ref "U$8") (pin "P$5") (pinfunction "VCCI/VCCO_P$5") (pintype "bidirectional"))
    )
    (net (code "46") (name "Net-(U$10-CLK32IN)") (class "Default")
      (node (ref "C22") (pin "2") (pinfunction "2_2") (pintype "passive"))
      (node (ref "R24") (pin "1") (pinfunction "1_1") (pintype "passive"))
      (node (ref "U$10") (pin "16") (pinfunction "CLK32IN_16") (pintype "bidirectional"))
      (node (ref "U$9") (pin "P$1") (pinfunction "1_P$1") (pintype "passive"))
    )
    (net (code "47") (name "Net-(U$10-CLK32OUT)") (class "Default")
      (node (ref "C21") (pin "2") (pinfunction "2_2") (pintype "passive"))
      (node (ref "R24") (pin "2") (pinfunction "2_2") (pintype "passive"))
      (node (ref "U$10") (pin "15") (pinfunction "CLK32OUT_15") (pintype "bidirectional"))
      (node (ref "U$9") (pin "P$2") (pinfunction "2_P$2") (pintype "passive"))
    )
    (net (code "48") (name "Net-(U$10-RSTN)") (class "Default")
      (node (ref "C29") (pin "1") (pinfunction "1_1") (pintype "passive"))
      (node (ref "R31") (pin "1") (pinfunction "1_1") (pintype "passive"))
      (node (ref "U$10") (pin "13") (pinfunction "RSTN_13") (pintype "bidirectional"))
    )
    (net (code "49") (name "Net-(U$10-XIN)") (class "Default")
      (node (ref "C3") (pin "2") (pinfunction "2_2") (pintype "passive"))
      (node (ref "R4") (pin "2") (pinfunction "2_2") (pintype "passive"))
      (node (ref "U$10") (pin "1") (pinfunction "XIN_1") (pintype "bidirectional"))
      (node (ref "U$14") (pin "P$2") (pinfunction "2_P$2") (pintype "passive"))
    )
    (net (code "50") (name "Net-(U$10-XOUT)") (class "Default")
      (node (ref "C7") (pin "2") (pinfunction "2_2") (pintype "passive"))
      (node (ref "R4") (pin "1") (pinfunction "1_1") (pintype "passive"))
      (node (ref "U$10") (pin "2") (pinfunction "XOUT_2") (pintype "bidirectional"))
      (node (ref "U$14") (pin "P$1") (pinfunction "1_P$1") (pintype "passive"))
    )
    (net (code "51") (name "Net-(U$12-N_OUT)") (class "Default")
      (node (ref "U$12") (pin "2") (pinfunction "P_OUT_2") (pintype "bidirectional"))
      (node (ref "U$12") (pin "3") (pinfunction "N_OUT_3") (pintype "bidirectional"))
      (node (ref "U$2") (pin "P$4") (pinfunction "4G_P$4") (pintype "bidirectional"))
    )
    (net (code "52") (name "Net-(U$12-VDD)") (class "Default")
      (node (ref "C16") (pin "1") (pinfunction "1_1") (pintype "passive"))
      (node (ref "L8") (pin "2") (pinfunction "2_2") (pintype "passive"))
      (node (ref "U$12") (pin "1") (pinfunction "VDD_1") (pintype "bidirectional"))
    )
    (net (code "53") (name "Net-(U$13-G)") (class "Default")
      (node (ref "R2") (pin "1") (pinfunction "1_1") (pintype "passive"))
      (node (ref "R3") (pin "2") (pinfunction "2_2") (pintype "passive"))
      (node (ref "U$13") (pin "1") (pinfunction "G_1") (pintype "bidirectional"))
    )
    (net (code "54") (name "Net-(VR1-CCW)") (class "Default")
      (node (ref "R6") (pin "1") (pinfunction "1_1") (pintype "passive"))
      (node (ref "VR1") (pin "1") (pinfunction "CCW_1") (pintype "passive"))
    )
    (net (code "55") (name "Net-(VR1-CW)") (class "Default")
      (node (ref "R5") (pin "2") (pinfunction "2_2") (pintype "passive"))
      (node (ref "VR1") (pin "3") (pinfunction "CW_3") (pintype "passive"))
    )
    (net (code "56") (name "Net-(VR1-WIPER)") (class "Default")
      (node (ref "U$11") (pin "FB") (pinfunction "FB_FB") (pintype "bidirectional"))
      (node (ref "VR1") (pin "2") (pinfunction "WIPER_2") (pintype "passive"))
    )
    (net (code "57") (name "Net-(VR2-CCW)") (class "Default")
      (node (ref "R22") (pin "1") (pinfunction "1_1") (pintype "passive"))
      (node (ref "VR2") (pin "1") (pinfunction "CCW_1") (pintype "passive"))
    )
    (net (code "58") (name "Net-(VR2-CW)") (class "Default")
      (node (ref "R23") (pin "2") (pinfunction "2_2") (pintype "passive"))
      (node (ref "VR2") (pin "3") (pinfunction "CW_3") (pintype "passive"))
    )
    (net (code "59") (name "unconnected-(U$5-OFFSET-PadP$4)") (class "Default")
      (node (ref "U$5") (pin "P$4") (pinfunction "OFFSET_P$4") (pintype "bidirectional"))
    )
    (net (code "60") (name "unconnected-(U$7-NC-PadP$1)") (class "Default")
      (node (ref "U$7") (pin "P$1") (pinfunction "NC_P$1") (pintype "bidirectional"))
    )
    (net (code "61") (name "unconnected-(U$10-EN_START-Pad32)") (class "Default")
      (node (ref "U$10") (pin "32") (pinfunction "EN_START_32") (pintype "bidirectional"))
    )
    (net (code "62") (name "unconnected-(U$10-FIRE_DOWN-Pad6)") (class "Default")
      (node (ref "U$10") (pin "6") (pinfunction "FIRE_DOWN_6") (pintype "bidirectional"))
    )
    (net (code "63") (name "unconnected-(U$10-FIRE_IN-Pad7)") (class "Default")
      (node (ref "U$10") (pin "7") (pinfunction "FIRE_IN_7") (pintype "bidirectional"))
    )
    (net (code "64") (name "unconnected-(U$10-INT-Pad8)") (class "Default")
      (node (ref "U$10") (pin "8") (pinfunction "INT_8") (pintype "bidirectional"))
    )
    (net (code "65") (name "unconnected-(U$10-LOADT-Pad18)") (class "Default")
      (node (ref "U$10") (pin "18") (pinfunction "LOADT_18") (pintype "bidirectional"))
    )
    (net (code "66") (name "unconnected-(U$10-PT1-Pad24)") (class "Default")
      (node (ref "U$10") (pin "24") (pinfunction "PT1_24") (pintype "bidirectional"))
    )
    (net (code "67") (name "unconnected-(U$10-PT2-Pad23)") (class "Default")
      (node (ref "U$10") (pin "23") (pinfunction "PT2_23") (pintype "bidirectional"))
    )
    (net (code "68") (name "unconnected-(U$10-PT3-Pad20)") (class "Default")
      (node (ref "U$10") (pin "20") (pinfunction "PT3_20") (pintype "bidirectional"))
    )
    (net (code "69") (name "unconnected-(U$10-PT4-Pad19)") (class "Default")
      (node (ref "U$10") (pin "19") (pinfunction "PT4_19") (pintype "bidirectional"))
    )
    (net (code "70") (name "unconnected-(U$10-SENSET-Pad17)") (class "Default")
      (node (ref "U$10") (pin "17") (pinfunction "SENSET_17") (pintype "bidirectional"))
    )
    (net (code "71") (name "unconnected-(U$15-Pad1)") (class "Default")
      (node (ref "U$15") (pin "1") (pinfunction "1_1") (pintype "passive"))
    )
    (net (code "72") (name "unconnected-(U$15-Pad6)") (class "Default")
      (node (ref "U$15") (pin "6") (pinfunction "6_6") (pintype "passive"))
    )
    (net (code "73") (name "unconnected-(U$15-Pad7)") (class "Default")
      (node (ref "U$15") (pin "7") (pinfunction "7_7") (pintype "passive"))
    )
    (net (code "74") (name "unconnected-(U$16-Pad2)") (class "Default")
      (node (ref "U$16") (pin "2") (pinfunction "2_2") (pintype "passive"))
    )
    (net (code "75") (name "unconnected-(U$16-Pad3)") (class "Default")
      (node (ref "U$16") (pin "3") (pinfunction "3_3") (pintype "passive"))
    )
    (net (code "76") (name "unconnected-(U$16-Pad4)") (class "Default")
      (node (ref "U$16") (pin "4") (pinfunction "4_4") (pintype "passive"))
    )
    (net (code "77") (name "unconnected-(U$16-Pad5)") (class "Default")
      (node (ref "U$16") (pin "5") (pinfunction "5_5") (pintype "passive"))
    )
    (net (code "78") (name "unconnected-(U$16-Pad6)") (class "Default")
      (node (ref "U$16") (pin "6") (pinfunction "6_6") (pintype "passive"))
    )
    (net (code "79") (name "unconnected-(U$16-Pad7)") (class "Default")
      (node (ref "U$16") (pin "7") (pinfunction "7_7") (pintype "passive"))
    )
    (net (code "80") (name "unconnected-(U$16-Pad8)") (class "Default")
      (node (ref "U$16") (pin "8") (pinfunction "8_8") (pintype "passive"))
    )
    (net (code "81") (name "unconnected-(U$16-Pad9)") (class "Default")
      (node (ref "U$16") (pin "9") (pinfunction "9_9") (pintype "passive"))
    )
    (net (code "82") (name "unconnected-(U$17-Pad1)") (class "Default")
      (node (ref "U$17") (pin "1") (pinfunction "1_1") (pintype "passive"))
    )
    (net (code "83") (name "unconnected-(U$17-Pad2)") (class "Default")
      (node (ref "U$17") (pin "2") (pinfunction "2_2") (pintype "passive"))
    )
    (net (code "84") (name "unconnected-(U$17-Pad3)") (class "Default")
      (node (ref "U$17") (pin "3") (pinfunction "3_3") (pintype "passive"))
    )
    (net (code "85") (name "unconnected-(U$17-Pad4)") (class "Default")
      (node (ref "U$17") (pin "4") (pinfunction "4_4") (pintype "passive"))
    )
    (net (code "86") (name "unconnected-(U$17-Pad7)") (class "Default")
      (node (ref "U$17") (pin "7") (pinfunction "7_7") (pintype "passive"))
    )
    (net (code "87") (name "unconnected-(U$17-Pad8)") (class "Default")
      (node (ref "U$17") (pin "8") (pinfunction "8_8") (pintype "passive"))
    )
    (net (code "88") (name "unconnected-(U$17-Pad9)") (class "Default")
      (node (ref "U$17") (pin "9") (pinfunction "9_9") (pintype "passive"))
    )
    (net (code "89") (name "unconnected-(U$17-Pad10)") (class "Default")
      (node (ref "U$17") (pin "10") (pinfunction "10_10") (pintype "passive"))
    )
    (net (code "90") (name "unconnected-(U$17-Pad11)") (class "Default")
      (node (ref "U$17") (pin "11") (pinfunction "11_11") (pintype "passive"))
    )
    (net (code "91") (name "unconnected-(U$17-Pad12)") (class "Default")
      (node (ref "U$17") (pin "12") (pinfunction "12_12") (pintype "passive"))
    )
    (net (code "92") (name "unconnected-(U$17-Pad13)") (class "Default")
      (node (ref "U$17") (pin "13") (pinfunction "13_13") (pintype "passive"))
    )
    (net (code "93") (name "unconnected-(U$17-Pad15)") (class "Default")
      (node (ref "U$17") (pin "15") (pinfunction "15_15") (pintype "passive"))
    )
  )
)
